# TI_amp.net
KiCad netlist of a schematic drawn in EAGLE
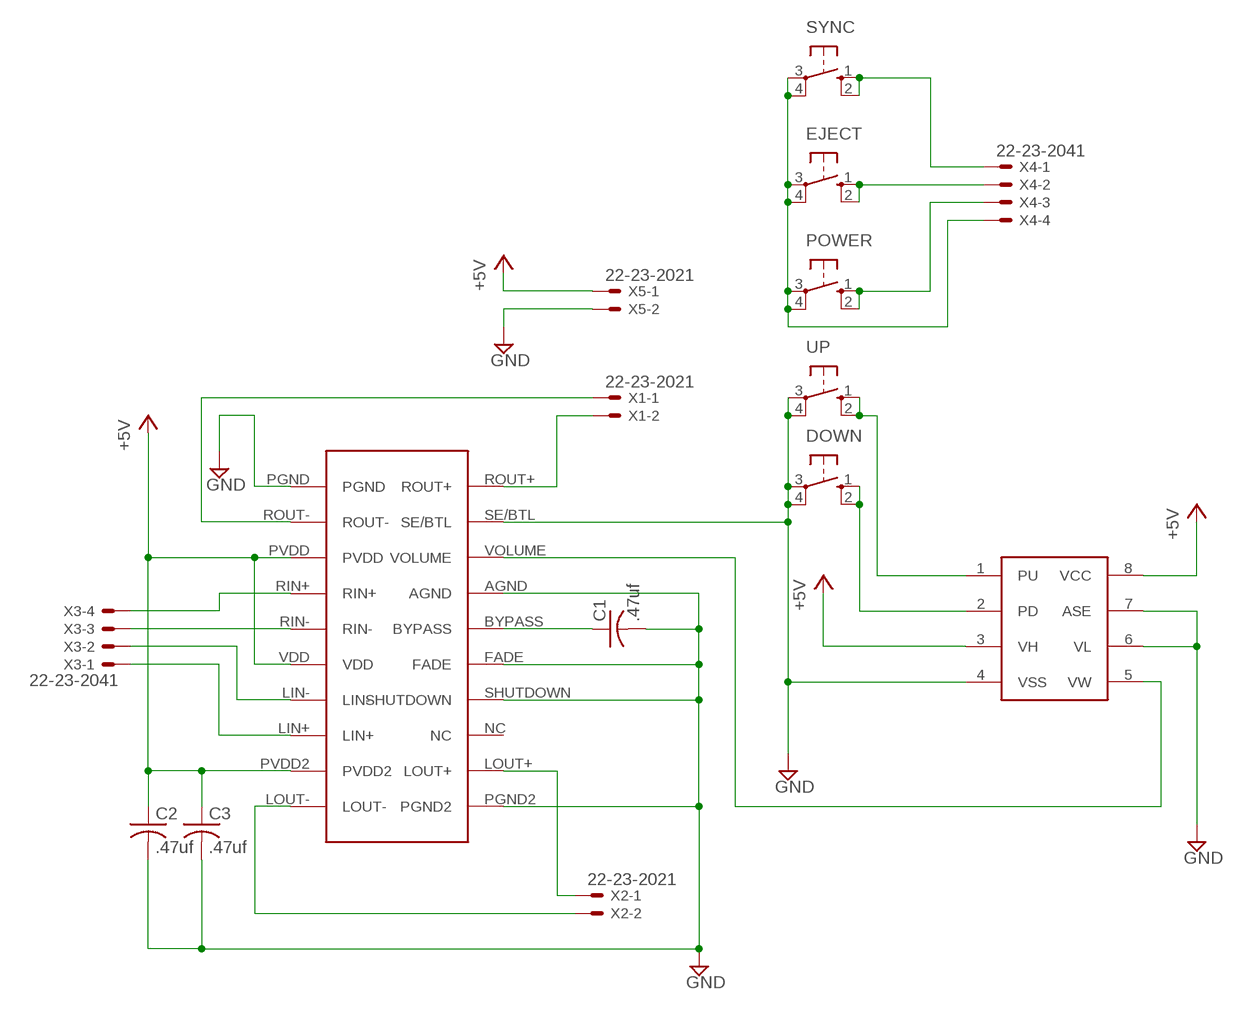
[diagram p0: schematic, sheet 1]

(export (version "E")
  (design (tool "Eeschema 10.0.6"))
  (components
    (comp (ref "C1")
      (value ".47uf")
      (footprint "eagle-import:C1206")
      (libsource (lib "eagle-import") (part "C-USC1206"))
    )
    (comp (ref "C2")
      (value ".47uf")
      (footprint "eagle-import:C1206")
      (libsource (lib "eagle-import") (part "C-USC1206"))
    )
    (comp (ref "C3")
      (value ".47uf")
      (footprint "eagle-import:C1206")
      (libsource (lib "eagle-import") (part "C-USC1206"))
    )
    (comp (ref "DOWN")
      (value "10-XX")
      (footprint "eagle-import:B3F-10XX")
      (fields (field (name "MPN") "B3F-1000"))
      (libsource (lib "eagle-import") (part "10-XX"))
    )
    (comp (ref "EJECT")
      (value "10-XX")
      (footprint "eagle-import:B3F-10XX")
      (fields (field (name "MPN") "B3F-1000"))
      (libsource (lib "eagle-import") (part "10-XX"))
    )
    (comp (ref "POWER")
      (value "10-XX")
      (footprint "eagle-import:B3F-10XX")
      (fields (field (name "MPN") "B3F-1000"))
      (libsource (lib "eagle-import") (part "10-XX"))
    )
    (comp (ref "SYNC")
      (value "10-XX")
      (footprint "eagle-import:B3F-10XX")
      (fields (field (name "MPN") "B3F-1000"))
      (libsource (lib "eagle-import") (part "10-XX"))
    )
    (comp (ref "U$1")
      (value "TPA6021A4")
      (footprint "eagle-import:DIP-20")
      (libsource (lib "eagle-import") (part "TPA6021A4"))
    )
    (comp (ref "U$2")
      (value "X9511")
      (footprint "eagle-import:SOIC-8")
      (libsource (lib "eagle-import") (part "X9511"))
    )
    (comp (ref "UP")
      (value "10-XX")
      (footprint "eagle-import:B3F-10XX")
      (fields (field (name "MPN") "B3F-1000"))
      (libsource (lib "eagle-import") (part "10-XX"))
    )
    (comp (ref "X1")
      (value "22-23-2021")
      (footprint "eagle-import:22-23-2021")
      (fields (field (name "MF") "MOLEX"))
      (libsource (lib "eagle-import") (part "22-23-2021"))
    )
    (comp (ref "X2")
      (value "22-23-2021")
      (footprint "eagle-import:22-23-2021")
      (fields (field (name "MF") "MOLEX"))
      (libsource (lib "eagle-import") (part "22-23-2021"))
    )
    (comp (ref "X3")
      (value "22-23-2041")
      (footprint "eagle-import:22-23-2041")
      (fields (field (name "MF") "MOLEX"))
      (libsource (lib "eagle-import") (part "22-23-2041"))
    )
    (comp (ref "X4")
      (value "22-23-2041")
      (footprint "eagle-import:22-23-2041")
      (fields (field (name "MF") "MOLEX"))
      (libsource (lib "eagle-import") (part "22-23-2041"))
    )
    (comp (ref "X5")
      (value "22-23-2021")
      (footprint "eagle-import:22-23-2021")
      (fields (field (name "MF") "MOLEX"))
      (libsource (lib "eagle-import") (part "22-23-2021"))
    )
  )
  (nets
    (net (code "1") (name "+5V") (class "Default")
      (node (ref "C2") (pin "1") (pinfunction "1_1") (pintype "passive"))
      (node (ref "C3") (pin "1") (pinfunction "1_1") (pintype "passive"))
      (node (ref "U$1") (pin "PVDD") (pinfunction "PVDD_PVDD") (pintype "bidirectional"))
      (node (ref "U$1") (pin "PVDD2") (pinfunction "PVDD2_PVDD2") (pintype "bidirectional"))
      (node (ref "U$1") (pin "VDD") (pinfunction "VDD_VDD") (pintype "bidirectional"))
      (node (ref "U$2") (pin "3") (pinfunction "VH_3") (pintype "bidirectional"))
      (node (ref "U$2") (pin "8") (pinfunction "VCC_8") (pintype "bidirectional"))
      (node (ref "X5") (pin "1") (pinfunction "S_1") (pintype "passive"))
    )
    (net (code "2") (name "GND") (class "Default")
      (node (ref "C1") (pin "2") (pinfunction "2_2") (pintype "passive"))
      (node (ref "C2") (pin "2") (pinfunction "2_2") (pintype "passive"))
      (node (ref "C3") (pin "2") (pinfunction "2_2") (pintype "passive"))
      (node (ref "DOWN") (pin "3") (pinfunction "P_3") (pintype "passive"))
      (node (ref "DOWN") (pin "4") (pinfunction "P1_4") (pintype "passive"))
      (node (ref "U$1") (pin "AGND") (pinfunction "AGND_AGND") (pintype "bidirectional"))
      (node (ref "U$1") (pin "FADE") (pinfunction "FADE_FADE") (pintype "bidirectional"))
      (node (ref "U$1") (pin "PGND") (pinfunction "PGND_PGND") (pintype "bidirectional"))
      (node (ref "U$1") (pin "PGND2") (pinfunction "PGND2_PGND2") (pintype "bidirectional"))
      (node (ref "U$1") (pin "SE/BTL") (pinfunction "SE/BTL_SE/BTL") (pintype "bidirectional"))
      (node (ref "U$1") (pin "SHUTDOWN") (pinfunction "SHUTDOWN_SHUTDOWN") (pintype "bidirectional"))
      (node (ref "U$2") (pin "4") (pinfunction "VSS_4") (pintype "bidirectional"))
      (node (ref "U$2") (pin "6") (pinfunction "VL_6") (pintype "bidirectional"))
      (node (ref "U$2") (pin "7") (pinfunction "ASE_7") (pintype "bidirectional"))
      (node (ref "UP") (pin "3") (pinfunction "P_3") (pintype "passive"))
      (node (ref "UP") (pin "4") (pinfunction "P1_4") (pintype "passive"))
      (node (ref "X5") (pin "2") (pinfunction "S_2") (pintype "passive"))
    )
    (net (code "3") (name "Net-(C1-Pad1)") (class "Default")
      (node (ref "C1") (pin "1") (pinfunction "1_1") (pintype "passive"))
      (node (ref "U$1") (pin "BYPASS") (pinfunction "BYPASS_BYPASS") (pintype "bidirectional"))
    )
    (net (code "4") (name "Net-(DOWN-S)") (class "Default")
      (node (ref "DOWN") (pin "1") (pinfunction "S_1") (pintype "passive"))
      (node (ref "DOWN") (pin "2") (pinfunction "S1_2") (pintype "passive"))
      (node (ref "U$2") (pin "2") (pinfunction "PD_2") (pintype "bidirectional"))
    )
    (net (code "5") (name "Net-(EJECT-P)") (class "Default")
      (node (ref "EJECT") (pin "3") (pinfunction "P_3") (pintype "passive"))
      (node (ref "EJECT") (pin "4") (pinfunction "P1_4") (pintype "passive"))
      (node (ref "POWER") (pin "3") (pinfunction "P_3") (pintype "passive"))
      (node (ref "POWER") (pin "4") (pinfunction "P1_4") (pintype "passive"))
      (node (ref "SYNC") (pin "3") (pinfunction "P_3") (pintype "passive"))
      (node (ref "SYNC") (pin "4") (pinfunction "P1_4") (pintype "passive"))
      (node (ref "X4") (pin "4") (pinfunction "S_4") (pintype "passive"))
    )
    (net (code "6") (name "Net-(EJECT-S)") (class "Default")
      (node (ref "EJECT") (pin "1") (pinfunction "S_1") (pintype "passive"))
      (node (ref "EJECT") (pin "2") (pinfunction "S1_2") (pintype "passive"))
      (node (ref "X4") (pin "2") (pinfunction "S_2") (pintype "passive"))
    )
    (net (code "7") (name "Net-(POWER-S)") (class "Default")
      (node (ref "POWER") (pin "1") (pinfunction "S_1") (pintype "passive"))
      (node (ref "POWER") (pin "2") (pinfunction "S1_2") (pintype "passive"))
      (node (ref "X4") (pin "3") (pinfunction "S_3") (pintype "passive"))
    )
    (net (code "8") (name "Net-(SYNC-S)") (class "Default")
      (node (ref "SYNC") (pin "1") (pinfunction "S_1") (pintype "passive"))
      (node (ref "SYNC") (pin "2") (pinfunction "S1_2") (pintype "passive"))
      (node (ref "X4") (pin "1") (pinfunction "S_1") (pintype "passive"))
    )
    (net (code "9") (name "Net-(U$2-PU)") (class "Default")
      (node (ref "U$2") (pin "1") (pinfunction "PU_1") (pintype "bidirectional"))
      (node (ref "UP") (pin "1") (pinfunction "S_1") (pintype "passive"))
      (node (ref "UP") (pin "2") (pinfunction "S1_2") (pintype "passive"))
    )
    (net (code "10") (name "Net-(U$2-VW)") (class "Default")
      (node (ref "U$1") (pin "VOLUME") (pinfunction "VOLUME_VOLUME") (pintype "bidirectional"))
      (node (ref "U$2") (pin "5") (pinfunction "VW_5") (pintype "bidirectional"))
    )
    (net (code "11") (name "Net-(X1A-S)") (class "Default")
      (node (ref "U$1") (pin "ROUT-") (pinfunction "ROUT-_ROUT-") (pintype "bidirectional"))
      (node (ref "X1") (pin "1") (pinfunction "S_1") (pintype "passive"))
    )
    (net (code "12") (name "Net-(X1B-S)") (class "Default")
      (node (ref "U$1") (pin "ROUT+") (pinfunction "ROUT+_ROUT+") (pintype "bidirectional"))
      (node (ref "X1") (pin "2") (pinfunction "S_2") (pintype "passive"))
    )
    (net (code "13") (name "Net-(X2A-S)") (class "Default")
      (node (ref "U$1") (pin "LOUT+") (pinfunction "LOUT+_LOUT+") (pintype "bidirectional"))
      (node (ref "X2") (pin "1") (pinfunction "S_1") (pintype "passive"))
    )
    (net (code "14") (name "Net-(X2B-S)") (class "Default")
      (node (ref "U$1") (pin "LOUT-") (pinfunction "LOUT-_LOUT-") (pintype "bidirectional"))
      (node (ref "X2") (pin "2") (pinfunction "S_2") (pintype "passive"))
    )
    (net (code "15") (name "Net-(X3A-S)") (class "Default")
      (node (ref "U$1") (pin "LIN+") (pinfunction "LIN+_LIN+") (pintype "bidirectional"))
      (node (ref "X3") (pin "1") (pinfunction "S_1") (pintype "passive"))
    )
    (net (code "16") (name "Net-(X3B-S)") (class "Default")
      (node (ref "U$1") (pin "LIN-") (pinfunction "LIN-_LIN-") (pintype "bidirectional"))
      (node (ref "X3") (pin "2") (pinfunction "S_2") (pintype "passive"))
    )
    (net (code "17") (name "Net-(X3C-S)") (class "Default")
      (node (ref "U$1") (pin "RIN-") (pinfunction "RIN-_RIN-") (pintype "bidirectional"))
      (node (ref "X3") (pin "3") (pinfunction "S_3") (pintype "passive"))
    )
    (net (code "18") (name "Net-(X3D-S)") (class "Default")
      (node (ref "U$1") (pin "RIN+") (pinfunction "RIN+_RIN+") (pintype "bidirectional"))
      (node (ref "X3") (pin "4") (pinfunction "S_4") (pintype "passive"))
    )
    (net (code "19") (name "unconnected-(U$1-PadNC)") (class "Default")
      (node (ref "U$1") (pin "NC") (pinfunction "NC_NC") (pintype "bidirectional"))
    )
  )
)
